# 02_Top_Level.net
KiCad netlist of a schematic drawn in Altium Designer
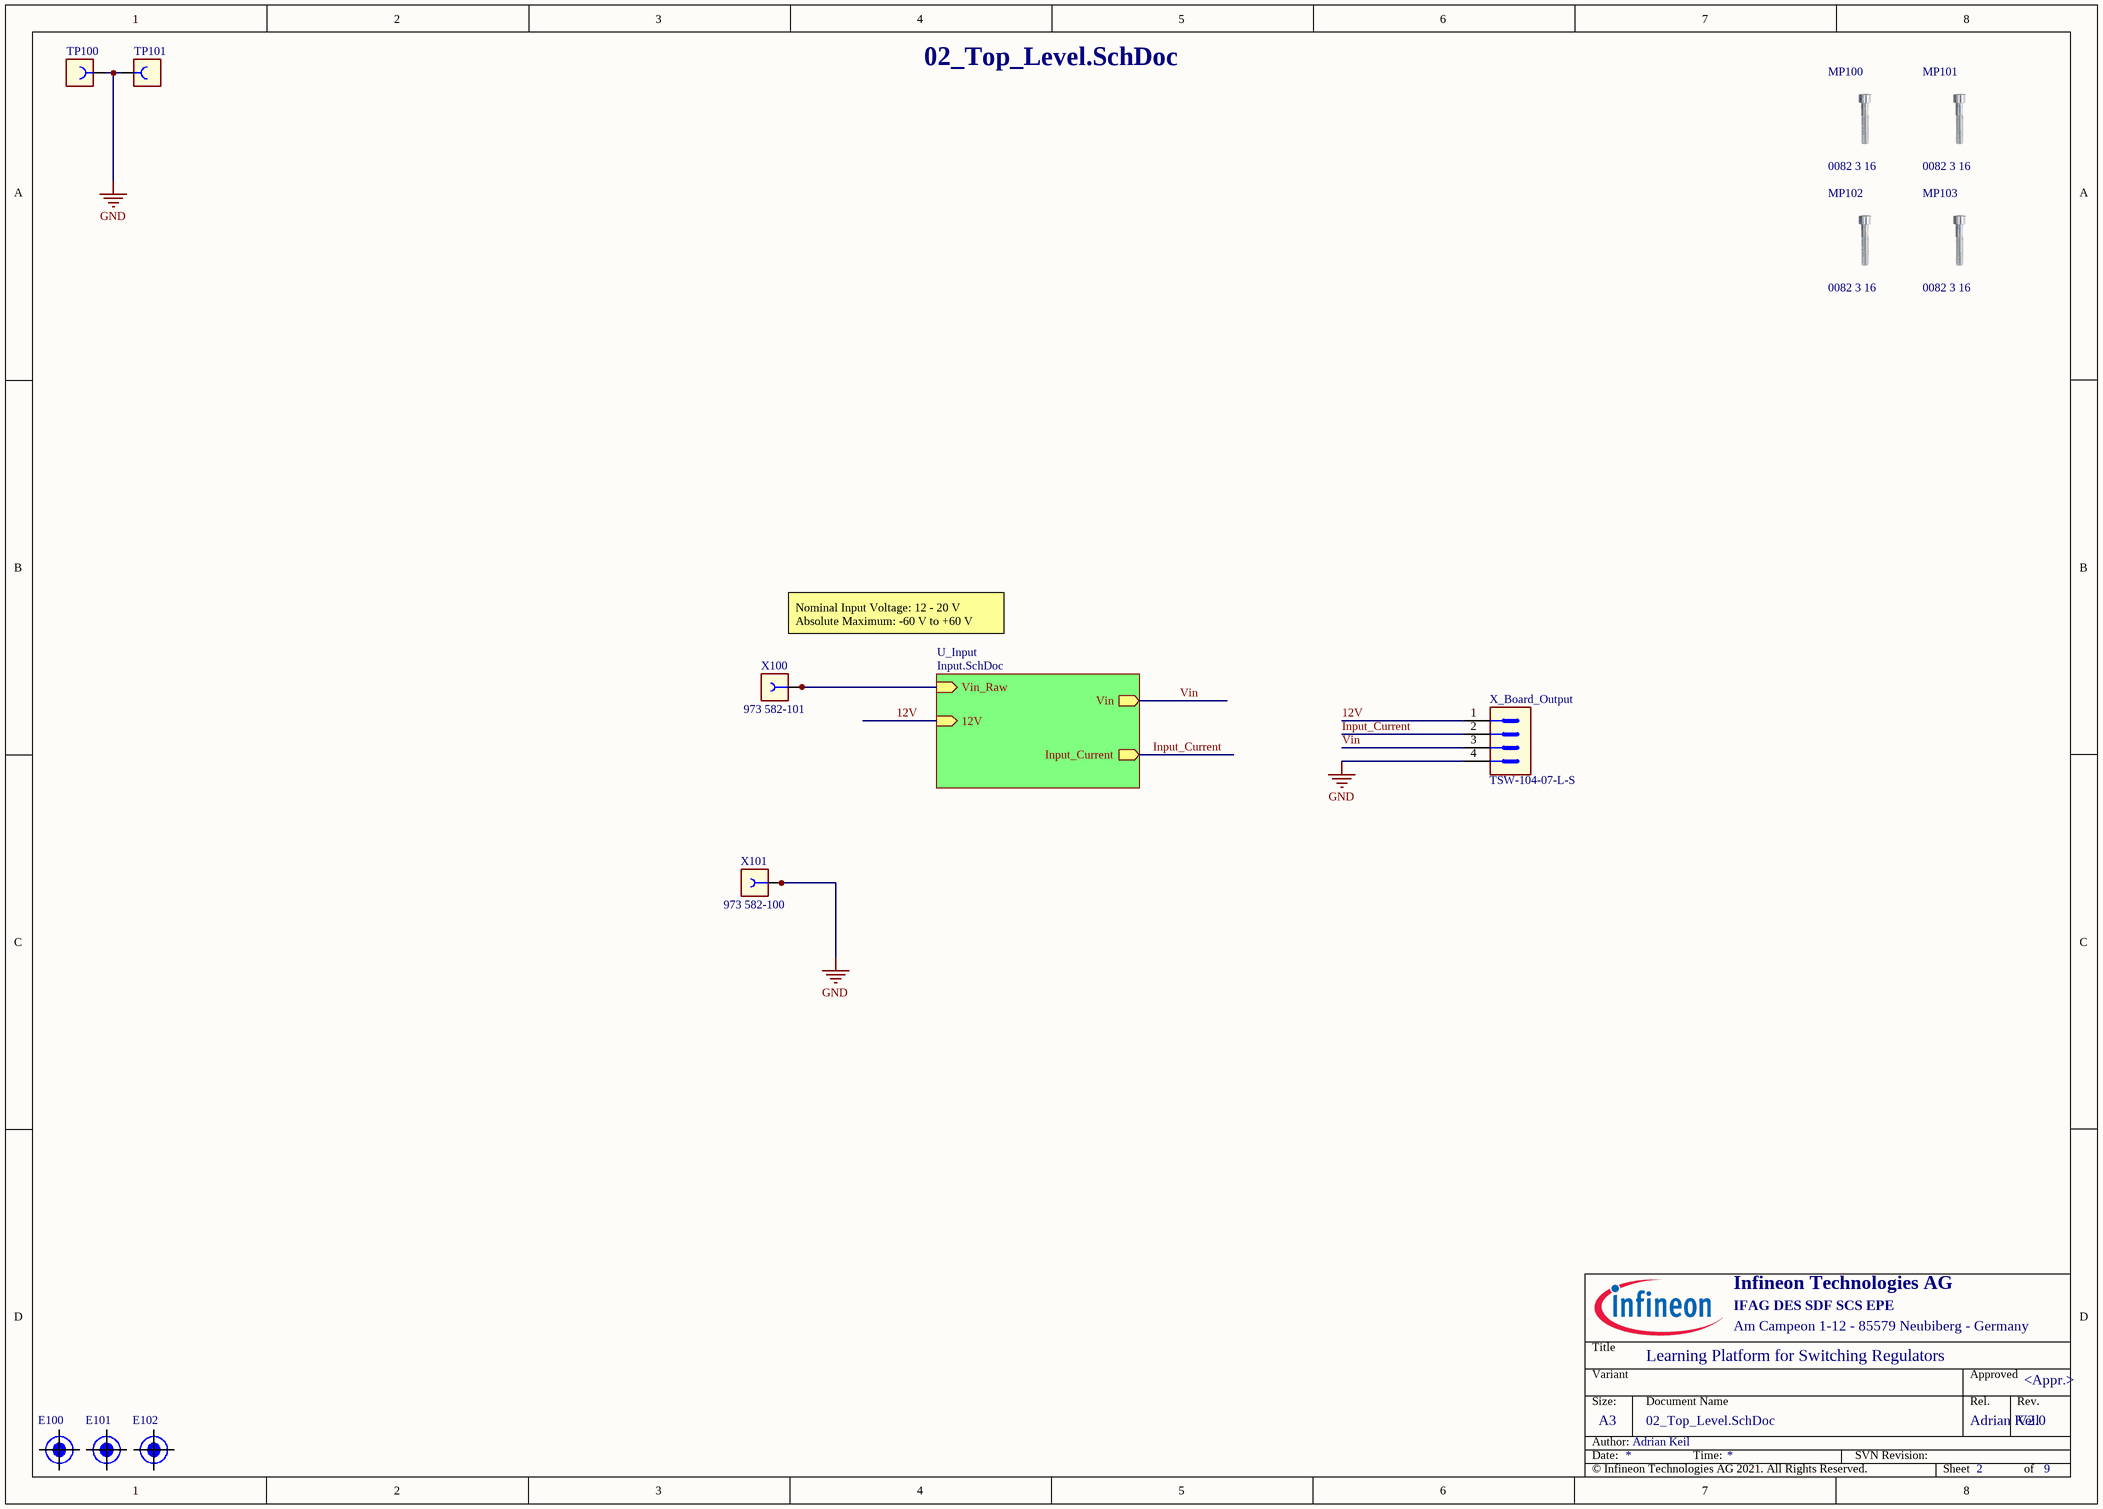
[diagram p0: 02_Top_Level.SchDoc]

(export (version "E")
  (design (tool "Eeschema 10.0.6"))
  (components
    (comp (ref "E100")
      (value "~")
      (footprint "fiducial")
      (description "Fiducial Mark")
      (fields
        (field (name "LEGACY PARTNUMBER") "MEC10000008")
        (field (name "MANUFACTURER") "Infineon Technologies")
      )
      (libsource (lib "PCBLibraryData") (part "fiducial"))
    )
    (comp (ref "E101")
      (value "~")
      (footprint "fiducial")
      (description "Fiducial Mark")
      (fields
        (field (name "LEGACY PARTNUMBER") "MEC10000008")
        (field (name "MANUFACTURER") "Infineon Technologies")
      )
      (libsource (lib "PCBLibraryData") (part "fiducial"))
    )
    (comp (ref "E102")
      (value "~")
      (footprint "fiducial")
      (description "Fiducial Mark")
      (fields
        (field (name "LEGACY PARTNUMBER") "MEC10000008")
        (field (name "MANUFACTURER") "Infineon Technologies")
      )
      (libsource (lib "PCBLibraryData") (part "fiducial"))
    )
    (comp (ref "MP100")
      (value "0082 3 16")
      (footprint "SCREW_0082 3 16_NPTH")
      (description "Cheese Head Screw With Hexagon Socket, DIN 912 (ISO 4762), M3, 16mm length")
      (fields
        (field (name "LEGACY PARTNUMBER") "MEC10000167")
        (field (name "MANUFACTURER") "Wurth Elektronik")
      )
      (libsource (lib "PCBLibraryData") (part "Screw_0082 3 16"))
    )
    (comp (ref "MP101")
      (value "0082 3 16")
      (footprint "SCREW_0082 3 16_NPTH")
      (description "Cheese Head Screw With Hexagon Socket, DIN 912 (ISO 4762), M3, 16mm length")
      (fields
        (field (name "LEGACY PARTNUMBER") "MEC10000167")
        (field (name "MANUFACTURER") "Wurth Elektronik")
      )
      (libsource (lib "PCBLibraryData") (part "Screw_0082 3 16"))
    )
    (comp (ref "MP102")
      (value "0082 3 16")
      (footprint "SCREW_0082 3 16_NPTH")
      (description "Cheese Head Screw With Hexagon Socket, DIN 912 (ISO 4762), M3, 16mm length")
      (fields
        (field (name "LEGACY PARTNUMBER") "MEC10000167")
        (field (name "MANUFACTURER") "Wurth Elektronik")
      )
      (libsource (lib "PCBLibraryData") (part "Screw_0082 3 16"))
    )
    (comp (ref "MP103")
      (value "0082 3 16")
      (footprint "SCREW_0082 3 16_NPTH")
      (description "Cheese Head Screw With Hexagon Socket, DIN 912 (ISO 4762), M3, 16mm length")
      (fields
        (field (name "LEGACY PARTNUMBER") "MEC10000167")
        (field (name "MANUFACTURER") "Wurth Elektronik")
      )
      (libsource (lib "PCBLibraryData") (part "Screw_0082 3 16"))
    )
    (comp (ref "TP100")
      (value "5011")
      (footprint "CON-THT-TP-5011")
      (description "PC Test Point-Multipurpose THT, Black")
      (fields
        (field (name "LEGACY PARTNUMBER") "CON01500530")
        (field (name "MANUFACTURER") "Keystone Electronics Corp.")
      )
      (libsource (lib "PCBLibraryData") (part "connector_1_f"))
    )
    (comp (ref "TP101")
      (value "5011")
      (footprint "CON-THT-TP-5011")
      (description "PC Test Point-Multipurpose THT, Black")
      (fields
        (field (name "LEGACY PARTNUMBER") "CON01500530")
        (field (name "MANUFACTURER") "Keystone Electronics Corp.")
      )
      (libsource (lib "") (part "connector_1_f_1"))
    )
    (comp (ref "X100")
      (value "973 582-101")
      (footprint "CON-THT-973 582- 101")
      (description "Banana Socket, Red, 17.5mm Pitch")
      (fields
        (field (name "LEGACY PARTNUMBER") "CON01500041")
        (field (name "MANUFACTURER") "Hirschmann Test & Measurement")
      )
      (libsource (lib "PCBLibraryData") (part "soc_banana_2p"))
    )
    (comp (ref "X101")
      (value "973 582-100")
      (footprint "CON-THT-973 582- 100")
      (description "Banana Socket, black, 17.5mm Pitch")
      (fields
        (field (name "LEGACY PARTNUMBER") "CON01500045")
        (field (name "MANUFACTURER") "Hirschmann Test & Measurement")
      )
      (libsource (lib "PCBLibraryData") (part "soc_banana_2p"))
    )
    (comp (ref "X_Board_Output")
      (value "TSW-104-07-L-S")
      (footprint "HDRV4W64P254_1X4_1022X254X838B")
      (description "Through hole .025 SQ Post Header, 2.54mm pitch, 4 pin, vertical, single row")
      (fields (field (name "LEGACY PARTNUMBER") "CON01500102") (field (name "MANUFACTURER") "Samtec"))
      (libsource (lib "PCBLibraryData") (part "Header 4"))
    )
  )
  (nets
    (net (code "1") (name "/12V") (class "Default")
      (node (ref "X_Board_Output") (pin "1") (pinfunction "1_1") (pintype "passive"))
    )
    (net (code "2") (name "/Input_Current") (class "Default")
      (node (ref "X_Board_Output") (pin "2") (pinfunction "2_2") (pintype "passive"))
    )
    (net (code "3") (name "/Vin") (class "Default")
      (node (ref "X_Board_Output") (pin "3") (pinfunction "3_3") (pintype "passive"))
    )
    (net (code "4") (name "/Vin_Raw") (class "Default")
      (node (ref "X100") (pin "1") (pinfunction "1_1") (pintype "passive"))
      (node (ref "X100") (pin "2") (pinfunction "2_2") (pintype "passive"))
    )
    (net (code "5") (name "GND") (class "Default")
      (node (ref "TP100") (pin "1") (pinfunction "1_1") (pintype "passive"))
      (node (ref "TP101") (pin "1") (pinfunction "1_1") (pintype "passive"))
      (node (ref "X101") (pin "1") (pinfunction "1_1") (pintype "passive"))
      (node (ref "X101") (pin "2") (pinfunction "2_2") (pintype "passive"))
      (node (ref "X_Board_Output") (pin "4") (pinfunction "4_4") (pintype "passive"))
    )
    (net (code "6") (name "unconnected-(E100-Pad1)") (class "Default")
      (node (ref "E100") (pin "1") (pinfunction "1_1") (pintype "passive"))
    )
    (net (code "7") (name "unconnected-(E101-Pad1)") (class "Default")
      (node (ref "E101") (pin "1") (pinfunction "1_1") (pintype "passive"))
    )
    (net (code "8") (name "unconnected-(E102-Pad1)") (class "Default")
      (node (ref "E102") (pin "1") (pinfunction "1_1") (pintype "passive"))
    )
  )
)
